# Double_Buffer.net
KiCad netlist of a schematic drawn in Altium Designer
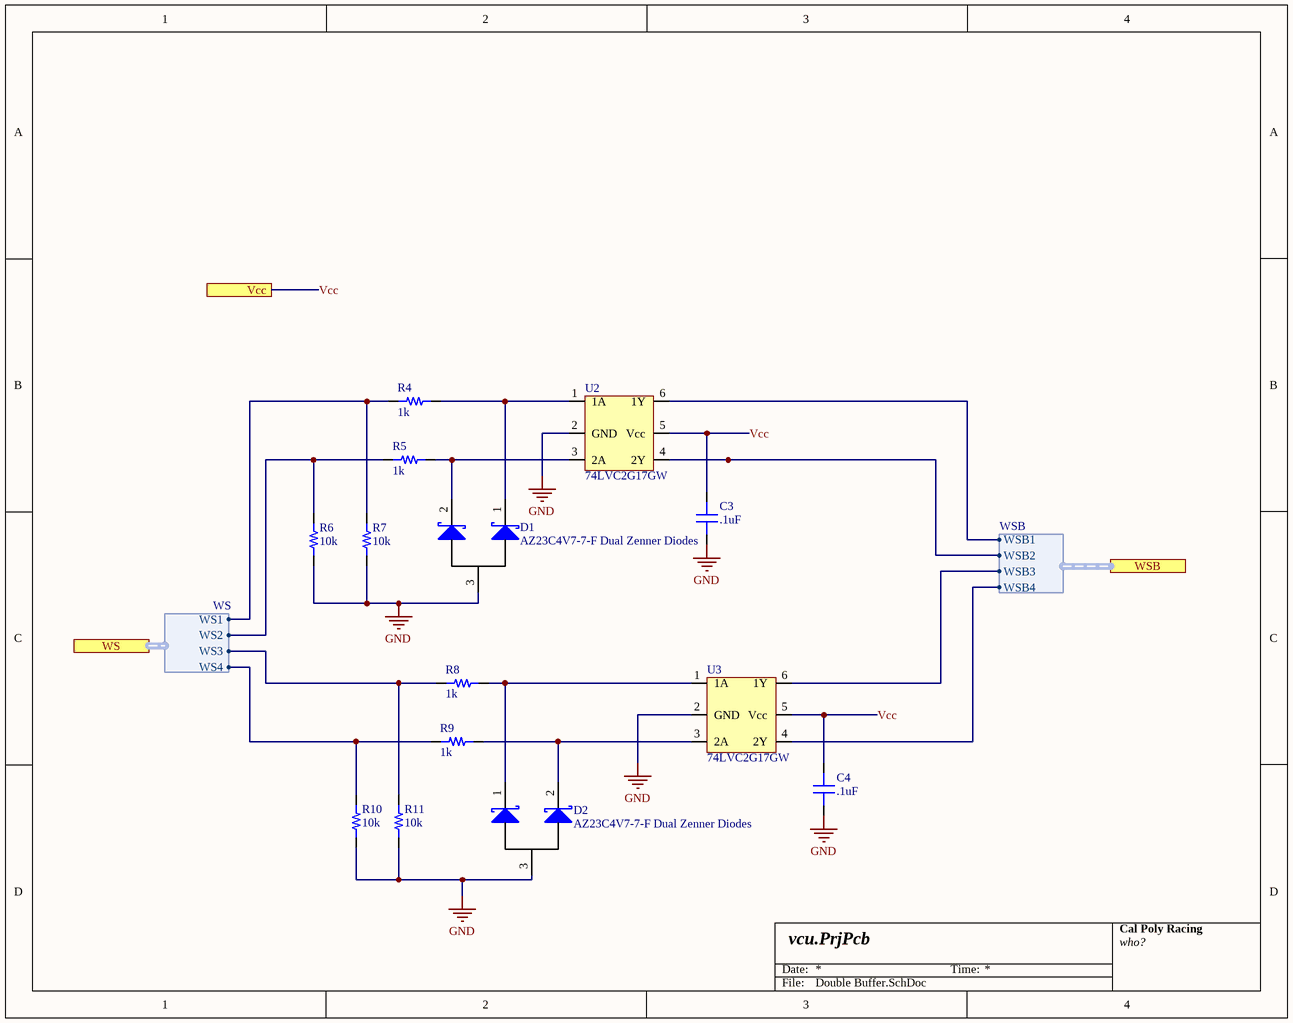
[diagram p0: Double Buffer.SchDoc]

(export (version "E")
  (design (tool "Eeschema 10.0.6"))
  (components
    (comp (ref "C3")
      (value "capacitor")
      (footprint "0603")
      (description "Generic 0603 capacitor")
      (fields (field (name "CAPACITANCE") ".1uF") (field (name "VOLTAGE") "50"))
      (libsource (lib "altlib") (part "capacitor"))
    )
    (comp (ref "C4")
      (value "capacitor")
      (footprint "0603")
      (description "Generic 0603 capacitor")
      (fields (field (name "CAPACITANCE") ".1uF") (field (name "VOLTAGE") "50"))
      (libsource (lib "altlib") (part "capacitor"))
    )
    (comp (ref "D1")
      (value "AZ23C4V7-7-F Dual Zenner Diodes")
      (footprint "SOT23-3")
      (description "DIODE ZENER ARRAY 4.7V SOT23-3")
      (libsource (lib "altlib") (part "AZ23C4V7-7-F Dual Zenner Diodes"))
    )
    (comp (ref "D2")
      (value "AZ23C4V7-7-F Dual Zenner Diodes")
      (footprint "SOT23-3")
      (description "DIODE ZENER ARRAY 4.7V SOT23-3")
      (libsource (lib "altlib") (part "AZ23C4V7-7-F Dual Zenner Diodes"))
    )
    (comp (ref "R4")
      (value "1k")
      (footprint "RES 0603/1608")
      (fields (field (name "RESISTANCE") "1k"))
      (libsource (lib "altlib") (part "Resistor"))
    )
    (comp (ref "R5")
      (value "1k")
      (footprint "RES 0603/1608")
      (fields (field (name "RESISTANCE") "1k"))
      (libsource (lib "altlib") (part "Resistor"))
    )
    (comp (ref "R6")
      (value "10k")
      (footprint "RES 0603/1608")
      (fields (field (name "RESISTANCE") "10k"))
      (libsource (lib "altlib") (part "Resistor"))
    )
    (comp (ref "R7")
      (value "10k")
      (footprint "RES 0603/1608")
      (fields (field (name "RESISTANCE") "10k"))
      (libsource (lib "altlib") (part "Resistor"))
    )
    (comp (ref "R8")
      (value "1k")
      (footprint "RES 0603/1608")
      (fields (field (name "RESISTANCE") "1k"))
      (libsource (lib "altlib") (part "Resistor"))
    )
    (comp (ref "R9")
      (value "1k")
      (footprint "RES 0603/1608")
      (fields (field (name "RESISTANCE") "1k"))
      (libsource (lib "altlib") (part "Resistor"))
    )
    (comp (ref "R10")
      (value "10k")
      (footprint "RES 0603/1608")
      (fields (field (name "RESISTANCE") "10k"))
      (libsource (lib "altlib") (part "Resistor"))
    )
    (comp (ref "R11")
      (value "10k")
      (footprint "RES 0603/1608")
      (fields (field (name "RESISTANCE") "10k"))
      (libsource (lib "altlib") (part "Resistor"))
    )
    (comp (ref "U2")
      (value "74LVC2G17GW")
      (footprint "TSOP95P280X110-6N")
      (description "Buffer, Non-Inverting 2 Element 1 Bit per Element Push-Pull Output 6-TSSOP")
      (fields (field (name "CREATEDBY") "Nolan") (field (name "UPDATEDBY") "Nolan"))
      (libsource (lib "altlib") (part "74LVC2G17GW"))
    )
    (comp (ref "U3")
      (value "74LVC2G17GW")
      (footprint "TSOP95P280X110-6N")
      (description "Buffer, Non-Inverting 2 Element 1 Bit per Element Push-Pull Output 6-TSSOP")
      (fields (field (name "CREATEDBY") "Nolan") (field (name "UPDATEDBY") "Nolan"))
      (libsource (lib "altlib") (part "74LVC2G17GW"))
    )
  )
  (nets
    (net (code "3") (name "/Vcc") (class "Default")
      (node (ref "C3") (pin "2") (pinfunction "2_2") (pintype "passive"))
      (node (ref "C4") (pin "2") (pinfunction "2_2") (pintype "passive"))
      (node (ref "U2") (pin "5") (pinfunction "Vcc_5") (pintype "passive"))
      (node (ref "U3") (pin "5") (pinfunction "Vcc_5") (pintype "passive"))
    )
    (net (code "4") (name "/WS1") (class "Default")
      (node (ref "R4") (pin "1") (pinfunction "1_1") (pintype "passive"))
      (node (ref "R7") (pin "2") (pinfunction "2_2") (pintype "passive"))
    )
    (net (code "5") (name "/WS2") (class "Default")
      (node (ref "R5") (pin "1") (pinfunction "1_1") (pintype "passive"))
      (node (ref "R6") (pin "2") (pinfunction "2_2") (pintype "passive"))
    )
    (net (code "6") (name "/WS3") (class "Default")
      (node (ref "R11") (pin "2") (pinfunction "2_2") (pintype "passive"))
      (node (ref "R8") (pin "1") (pinfunction "1_1") (pintype "passive"))
    )
    (net (code "7") (name "/WS4") (class "Default")
      (node (ref "R10") (pin "2") (pinfunction "2_2") (pintype "passive"))
      (node (ref "R9") (pin "1") (pinfunction "1_1") (pintype "passive"))
    )
    (net (code "8") (name "/WSB1") (class "Default")
      (node (ref "U2") (pin "6") (pinfunction "1Y_6") (pintype "passive"))
    )
    (net (code "9") (name "/WSB2") (class "Default")
      (node (ref "U2") (pin "4") (pinfunction "2Y_4") (pintype "passive"))
    )
    (net (code "10") (name "/WSB3") (class "Default")
      (node (ref "U3") (pin "6") (pinfunction "1Y_6") (pintype "passive"))
    )
    (net (code "11") (name "/WSB4") (class "Default")
      (node (ref "U3") (pin "4") (pinfunction "2Y_4") (pintype "passive"))
    )
    (net (code "14") (name "GND") (class "Default")
      (node (ref "C3") (pin "1") (pinfunction "1_1") (pintype "passive"))
      (node (ref "C4") (pin "1") (pinfunction "1_1") (pintype "passive"))
      (node (ref "D1") (pin "3") (pinfunction "3_3") (pintype "passive"))
      (node (ref "D2") (pin "3") (pinfunction "3_3") (pintype "passive"))
      (node (ref "R10") (pin "1") (pinfunction "1_1") (pintype "passive"))
      (node (ref "R11") (pin "1") (pinfunction "1_1") (pintype "passive"))
      (node (ref "R6") (pin "1") (pinfunction "1_1") (pintype "passive"))
      (node (ref "R7") (pin "1") (pinfunction "1_1") (pintype "passive"))
      (node (ref "U2") (pin "2") (pinfunction "GND_2") (pintype "passive"))
      (node (ref "U3") (pin "2") (pinfunction "GND_2") (pintype "passive"))
    )
    (net (code "15") (name "Net-(U2-1A)") (class "Default")
      (node (ref "D1") (pin "1") (pinfunction "1_1") (pintype "passive"))
      (node (ref "R4") (pin "2") (pinfunction "2_2") (pintype "passive"))
      (node (ref "U2") (pin "1") (pinfunction "1A_1") (pintype "passive"))
    )
    (net (code "16") (name "Net-(U2-2A)") (class "Default")
      (node (ref "D1") (pin "2") (pinfunction "2_2") (pintype "passive"))
      (node (ref "R5") (pin "2") (pinfunction "2_2") (pintype "passive"))
      (node (ref "U2") (pin "3") (pinfunction "2A_3") (pintype "passive"))
    )
    (net (code "17") (name "Net-(U3-1A)") (class "Default")
      (node (ref "D2") (pin "1") (pinfunction "1_1") (pintype "passive"))
      (node (ref "R8") (pin "2") (pinfunction "2_2") (pintype "passive"))
      (node (ref "U3") (pin "1") (pinfunction "1A_1") (pintype "passive"))
    )
    (net (code "18") (name "Net-(U3-2A)") (class "Default")
      (node (ref "D2") (pin "2") (pinfunction "2_2") (pintype "passive"))
      (node (ref "R9") (pin "2") (pinfunction "2_2") (pintype "passive"))
      (node (ref "U3") (pin "3") (pinfunction "2A_3") (pintype "passive"))
    )
  )
)
